# SCH_ESP-32_2024-10-27.net
KiCad netlist of a schematic drawn in EasyEDA
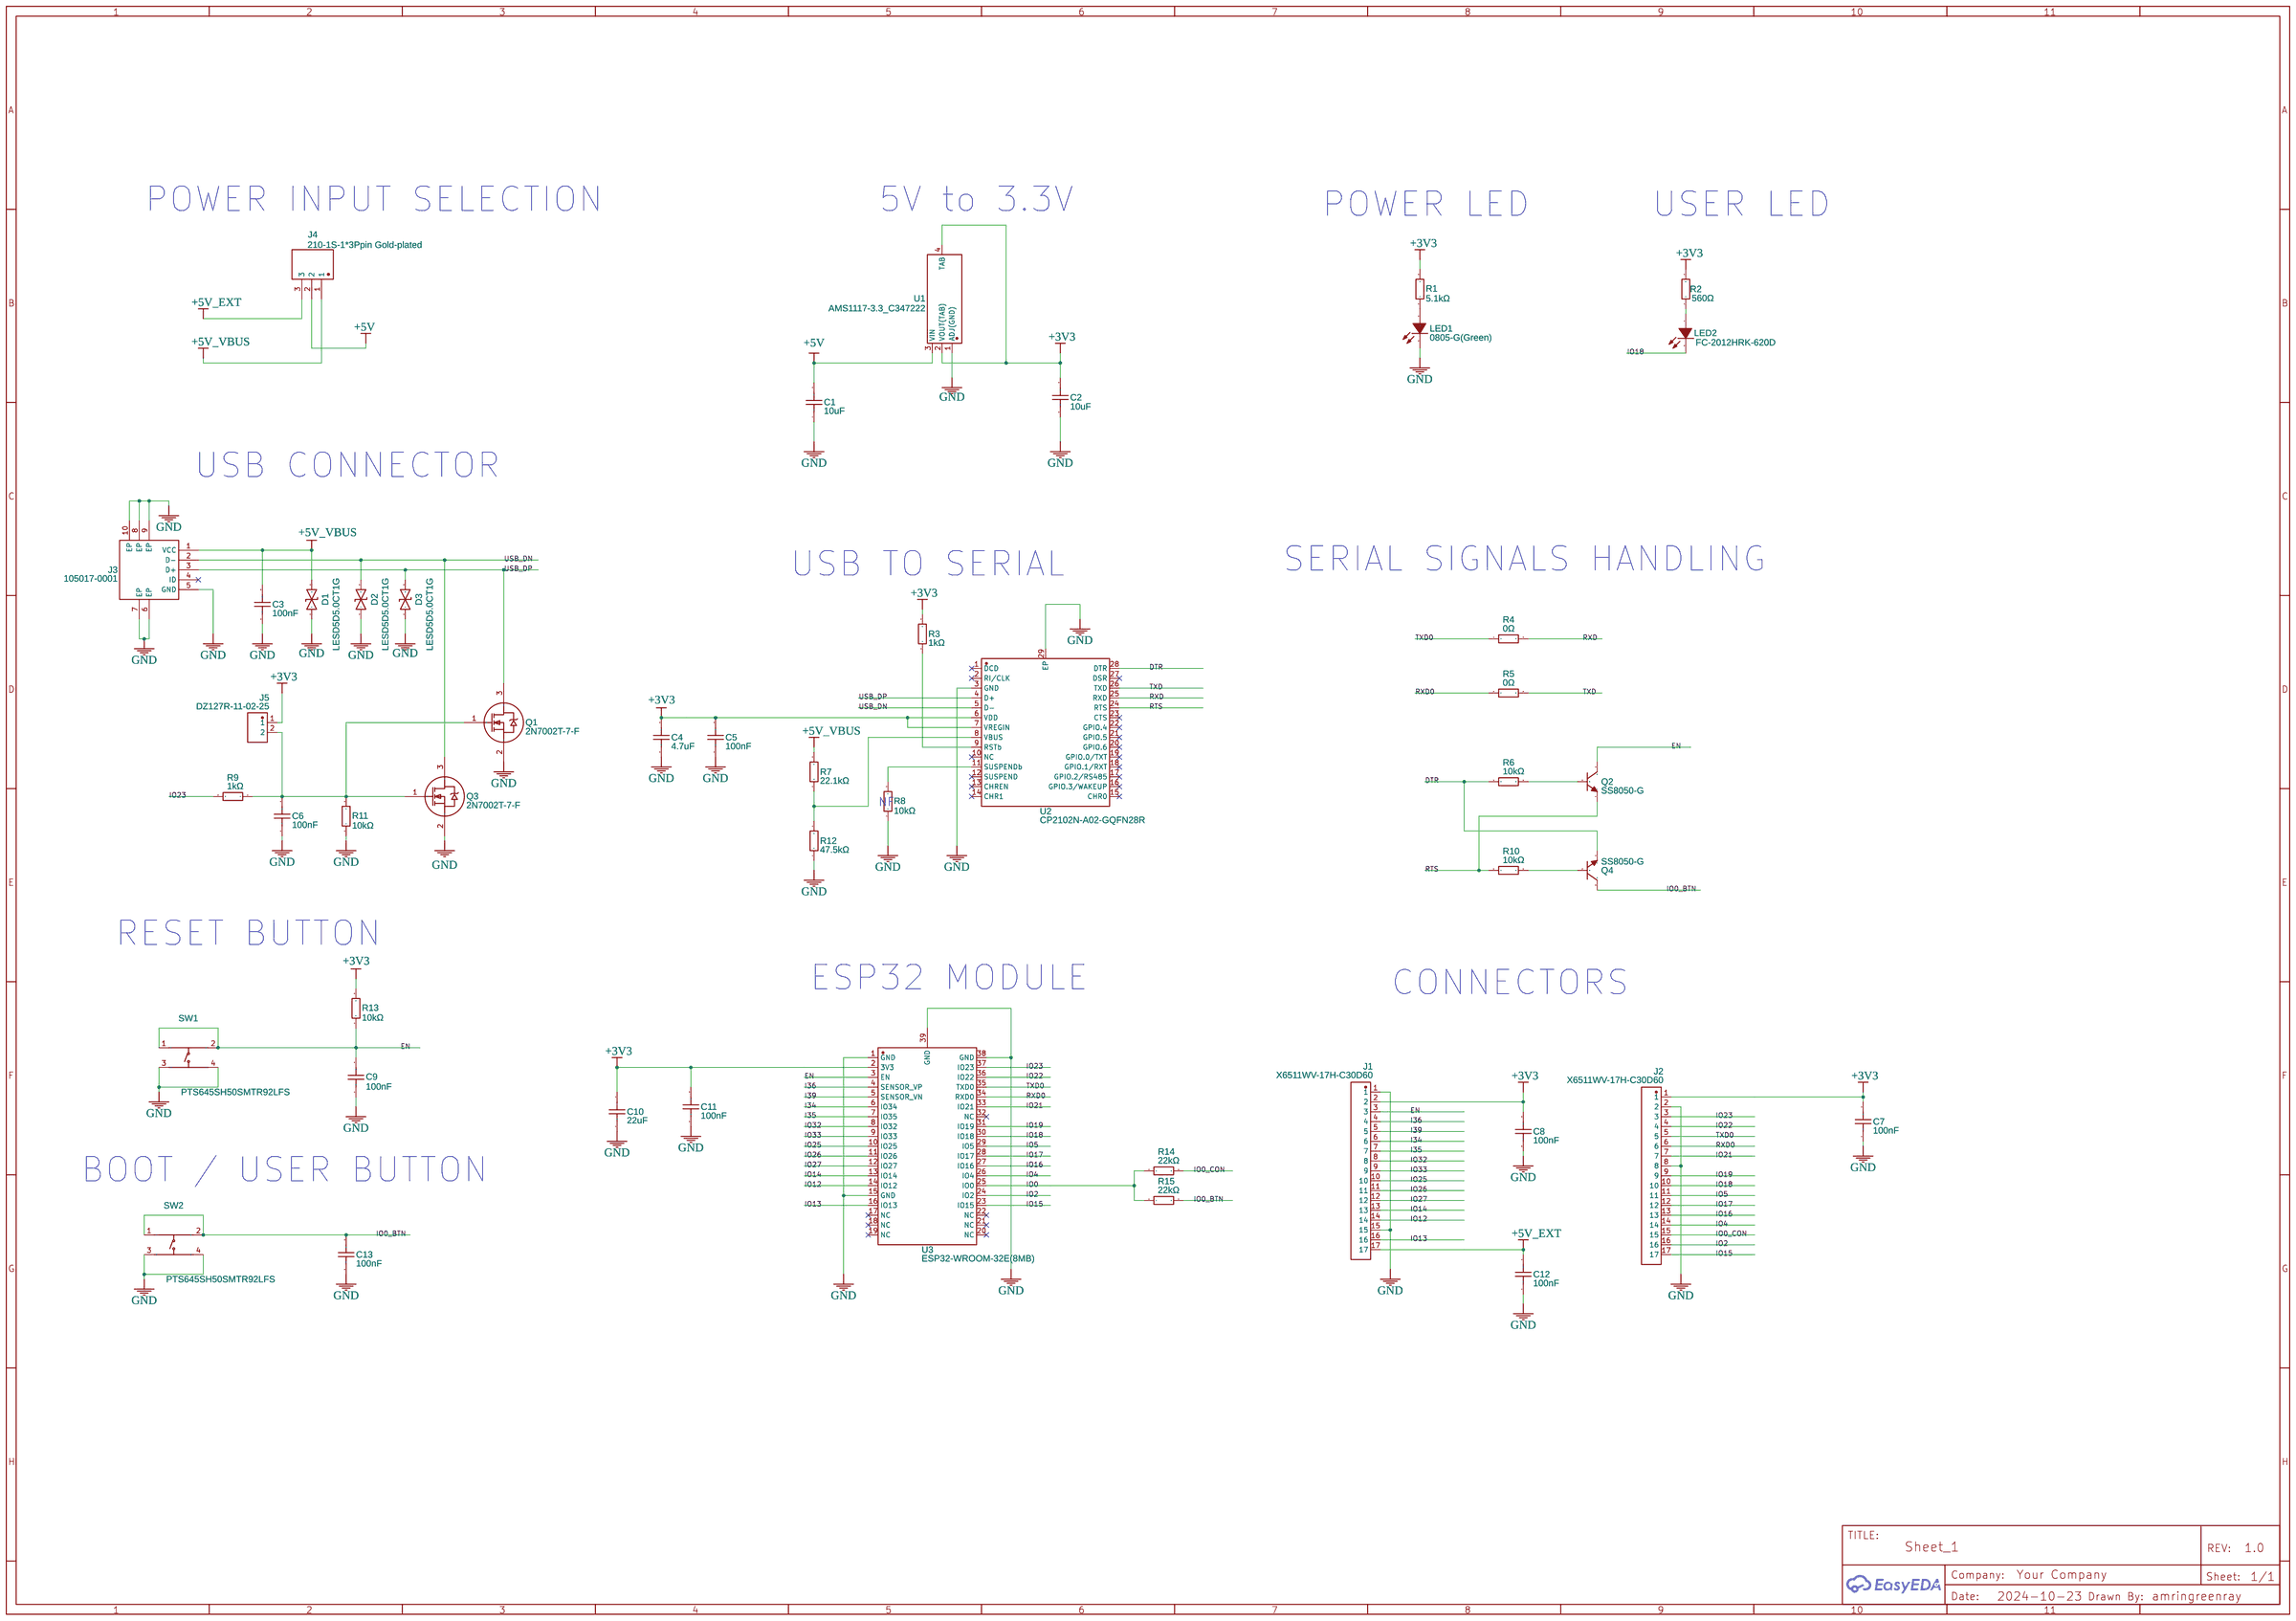
[diagram p0: schematic sheet]

(export (version "E")
  (design (tool "Eeschema 10.0.6"))
  (components
    (comp (ref "C1")
      (value "10uF")
      (fields
        (field (name "Manufacturer Part") "CL05A106MP5NUNC")
        (field (name "Manufacturer") "SAMSUNG(三星)")
      )
      (libsource (lib "") (part "CL05A106MP5NUNC_C315248"))
    )
    (comp (ref "C2")
      (value "10uF")
      (fields
        (field (name "Manufacturer Part") "CL05A106MP5NUNC")
        (field (name "Manufacturer") "SAMSUNG(三星)")
      )
      (libsource (lib "") (part "CL05A106MP5NUNC_C315248"))
    )
    (comp (ref "C3")
      (value "100nF")
      (fields
        (field (name "Manufacturer Part") "CL05B104KO5NNNC")
        (field (name "Manufacturer") "SAMSUNG(三星)")
      )
      (libsource (lib "") (part "CL05B104KO5NNNC"))
    )
    (comp (ref "C4")
      (value "4.7uF")
      (fields
        (field (name "Manufacturer Part") "CL05A475KP5NRNC")
        (field (name "Manufacturer") "SAMSUNG(三星)")
      )
      (libsource (lib "") (part "CL05A475KP5NRNC"))
    )
    (comp (ref "C5")
      (value "100nF")
      (fields
        (field (name "Manufacturer Part") "CL05B104KO5NNNC")
        (field (name "Manufacturer") "SAMSUNG(三星)")
      )
      (libsource (lib "") (part "CL05B104KO5NNNC"))
    )
    (comp (ref "C6")
      (value "100nF")
      (fields
        (field (name "Manufacturer Part") "CL05B104KO5NNNC")
        (field (name "Manufacturer") "SAMSUNG(三星)")
      )
      (libsource (lib "") (part "CL05B104KO5NNNC_1"))
    )
    (comp (ref "C7")
      (value "100nF")
      (fields
        (field (name "Manufacturer Part") "CL05B104KO5NNNC")
        (field (name "Manufacturer") "SAMSUNG(三星)")
      )
      (libsource (lib "") (part "CL05B104KO5NNNC"))
    )
    (comp (ref "C8")
      (value "100nF")
      (fields
        (field (name "Manufacturer Part") "CL05B104KO5NNNC")
        (field (name "Manufacturer") "SAMSUNG(三星)")
      )
      (libsource (lib "") (part "CL05B104KO5NNNC"))
    )
    (comp (ref "C9")
      (value "100nF")
      (fields
        (field (name "Manufacturer Part") "CL05B104KO5NNNC")
        (field (name "Manufacturer") "SAMSUNG(三星)")
      )
      (libsource (lib "") (part "CL05B104KO5NNNC"))
    )
    (comp (ref "C10")
      (value "22uF")
      (fields
        (field (name "Manufacturer Part") "CL21A226MAYNNNE")
        (field (name "Manufacturer") "SAMSUNG(三星)")
      )
      (libsource (lib "") (part "CL21A226MAYNNNE"))
    )
    (comp (ref "C11")
      (value "100nF")
      (fields
        (field (name "Manufacturer Part") "CL05B104KO5NNNC")
        (field (name "Manufacturer") "SAMSUNG(三星)")
      )
      (libsource (lib "") (part "CL05B104KO5NNNC"))
    )
    (comp (ref "C12")
      (value "100nF")
      (fields
        (field (name "Manufacturer Part") "CL05B104KO5NNNC")
        (field (name "Manufacturer") "SAMSUNG(三星)")
      )
      (libsource (lib "") (part "CL05B104KO5NNNC"))
    )
    (comp (ref "C13")
      (value "100nF")
      (fields
        (field (name "Manufacturer Part") "CL05B104KO5NNNC")
        (field (name "Manufacturer") "SAMSUNG(三星)")
      )
      (libsource (lib "") (part "CL05B104KO5NNNC"))
    )
    (comp (ref "D1")
      (value "LESD5D5.0CT1G")
      (fields (field (name "Manufacturer") "LRC(乐山无线电)"))
      (libsource (lib "") (part "LESD5D5.0CT1G"))
    )
    (comp (ref "D2")
      (value "LESD5D5.0CT1G")
      (fields (field (name "Manufacturer") "LRC(乐山无线电)"))
      (libsource (lib "") (part "LESD5D5.0CT1G"))
    )
    (comp (ref "D3")
      (value "LESD5D5.0CT1G")
      (fields (field (name "Manufacturer") "LRC(乐山无线电)"))
      (libsource (lib "") (part "LESD5D5.0CT1G"))
    )
    (comp (ref "J1")
      (value "X6511WV-17H-C30D60")
      (fields
        (field (name "Manufacturer Part") "X6511WV-17H-C60D30")
        (field (name "Manufacturer") "XKB Connection(中国星坤)")
      )
      (libsource (lib "") (part "X6511WV-17H-C30D60"))
    )
    (comp (ref "J2")
      (value "X6511WV-17H-C30D60")
      (fields
        (field (name "Manufacturer Part") "X6511WV-17H-C60D30")
        (field (name "Manufacturer") "XKB Connection(中国星坤)")
      )
      (libsource (lib "") (part "X6511WV-17H-C30D60"))
    )
    (comp (ref "J3")
      (value "105017-0001")
      (fields (field (name "Manufacturer Part") "1050170001") (field (name "Manufacturer") "MOLEX"))
      (libsource (lib "") (part "105017-0001"))
    )
    (comp (ref "J4")
      (value "210-1S-1*3Ppin Gold-plated")
      (fields (field (name "Manufacturer Part") "B-2101S03P-A110") (field (name "Manufacturer") "Ckmtw(灿科盟)"))
      (libsource (lib "") (part "210-1S-1*3Ppin Gold-plated"))
    )
    (comp (ref "J5")
      (value "DZ127R-11-02-25")
      (fields (field (name "Manufacturer") "DEALON(德艺隆)"))
      (libsource (lib "") (part "DZ127R-11-02-25"))
    )
    (comp (ref "LED1")
      (value "0805-G(Green)")
      (fields (field (name "Manufacturer Part") "LEDGREEN0805"))
      (libsource (lib "") (part "LEDGREEN0805"))
    )
    (comp (ref "LED2")
      (value "FC-2012HRK-620D")
      (fields (field (name "Manufacturer Part") "NCD0805R1") (field (name "Manufacturer") "国星光电"))
      (libsource (lib "") (part "FC-2012HRK-620D"))
    )
    (comp (ref "Q1")
      (value "2N7002T-7-F")
      (fields (field (name "Manufacturer") "DIODES(美台)"))
      (libsource (lib "") (part "2N7002T-7-F"))
    )
    (comp (ref "Q2")
      (value "SS8050-G")
      (fields (field (name "Manufacturer") "CJ(江苏长电/长晶)"))
      (libsource (lib "") (part "SS8050-G"))
    )
    (comp (ref "Q3")
      (value "2N7002T-7-F")
      (fields (field (name "Manufacturer") "DIODES(美台)"))
      (libsource (lib "") (part "2N7002T-7-F"))
    )
    (comp (ref "Q4")
      (value "SS8050-G")
      (fields (field (name "Manufacturer") "CJ(江苏长电/长晶)"))
      (libsource (lib "") (part "SS8050-G_1"))
    )
    (comp (ref "R1")
      (value "5.1kΩ")
      (fields
        (field (name "Manufacturer Part") "0402WGF5101TCE")
        (field (name "Manufacturer") "UNI-ROYAL(厚声)")
      )
      (libsource (lib "") (part "0402WGF5101TCE"))
    )
    (comp (ref "R2")
      (value "560Ω")
      (fields
        (field (name "Manufacturer Part") "0402WGF5600TCE")
        (field (name "Manufacturer") "UNI-ROYAL(厚声)")
      )
      (libsource (lib "") (part "0402WGF5600TCE"))
    )
    (comp (ref "R3")
      (value "1kΩ")
      (fields
        (field (name "Manufacturer Part") "0402WGF1001TCE")
        (field (name "Manufacturer") "UNI-ROYAL(厚声)")
      )
      (libsource (lib "") (part "0402WGF1001TCE"))
    )
    (comp (ref "R4")
      (value "0Ω")
      (fields
        (field (name "Manufacturer Part") "0402WGF0000TCE")
        (field (name "Manufacturer") "UNI-ROYAL(厚声)")
      )
      (libsource (lib "") (part "0402WGF0000TCE"))
    )
    (comp (ref "R5")
      (value "0Ω")
      (fields
        (field (name "Manufacturer Part") "0402WGF0000TCE")
        (field (name "Manufacturer") "UNI-ROYAL(厚声)")
      )
      (libsource (lib "") (part "0402WGF0000TCE"))
    )
    (comp (ref "R6")
      (value "10kΩ")
      (fields
        (field (name "Manufacturer Part") "0402WGF1002TCE")
        (field (name "Manufacturer") "UNI-ROYAL(厚声)")
      )
      (libsource (lib "") (part "0402WGF1002TCE"))
    )
    (comp (ref "R7")
      (value "22.1kΩ")
      (fields
        (field (name "Manufacturer Part") "0402WGF2212TCE")
        (field (name "Manufacturer") "UNI-ROYAL(厚声)")
      )
      (libsource (lib "") (part "0402WGF2212TCE"))
    )
    (comp (ref "R8")
      (value "10kΩ")
      (fields
        (field (name "Manufacturer Part") "0402WGF1002TCE")
        (field (name "Manufacturer") "UNI-ROYAL(厚声)")
      )
      (libsource (lib "") (part "0402WGF1002TCE_1"))
    )
    (comp (ref "R9")
      (value "1kΩ")
      (fields
        (field (name "Manufacturer Part") "0402WGF1001TCE")
        (field (name "Manufacturer") "UNI-ROYAL(厚声)")
      )
      (libsource (lib "") (part "0402WGF1001TCE_1"))
    )
    (comp (ref "R10")
      (value "10kΩ")
      (fields
        (field (name "Manufacturer Part") "0402WGF1002TCE")
        (field (name "Manufacturer") "UNI-ROYAL(厚声)")
      )
      (libsource (lib "") (part "0402WGF1002TCE"))
    )
    (comp (ref "R11")
      (value "10kΩ")
      (fields
        (field (name "Manufacturer Part") "0402WGF1002TCE")
        (field (name "Manufacturer") "UNI-ROYAL(厚声)")
      )
      (libsource (lib "") (part "0402WGF1002TCE_1"))
    )
    (comp (ref "R12")
      (value "47.5kΩ")
      (fields
        (field (name "Manufacturer Part") "0402WGF4752TCE")
        (field (name "Manufacturer") "UNI-ROYAL(厚声)")
      )
      (libsource (lib "") (part "0402WGF4752TCE"))
    )
    (comp (ref "R13")
      (value "10kΩ")
      (fields
        (field (name "Manufacturer Part") "0402WGF1002TCE")
        (field (name "Manufacturer") "UNI-ROYAL(厚声)")
      )
      (libsource (lib "") (part "0402WGF1002TCE_1"))
    )
    (comp (ref "R14")
      (value "22kΩ")
      (fields
        (field (name "Manufacturer Part") "0402WGF2202TCE")
        (field (name "Manufacturer") "UNI-ROYAL(厚声)")
      )
      (libsource (lib "") (part "0402WGF2202TCE"))
    )
    (comp (ref "R15")
      (value "22kΩ")
      (fields
        (field (name "Manufacturer Part") "0402WGF2202TCE")
        (field (name "Manufacturer") "UNI-ROYAL(厚声)")
      )
      (libsource (lib "") (part "0402WGF2202TCE"))
    )
    (comp (ref "SW1")
      (value "PTS645SH50SMTR92LFS")
      (fields (field (name "Manufacturer") "C&K"))
      (libsource (lib "") (part "PTS645SH50SMTR92LFS"))
    )
    (comp (ref "SW2")
      (value "PTS645SH50SMTR92LFS")
      (fields (field (name "Manufacturer") "C&K"))
      (libsource (lib "") (part "PTS645SH50SMTR92LFS"))
    )
    (comp (ref "U1")
      (value "AMS1117-3.3_C347222")
      (fields (field (name "Manufacturer Part") "AMS1117-3.3") (field (name "Manufacturer") "UMW(友台半导体)"))
      (libsource (lib "") (part "AMS1117-3.3_C347222"))
    )
    (comp (ref "U2")
      (value "CP2102N-A02-GQFN28R")
      (fields (field (name "Manufacturer") "SKYWORKS/SILICON LABS(芯科)"))
      (libsource (lib "") (part "CP2102N-A02-GQFN28R"))
    )
    (comp (ref "U3")
      (value "ESP32-WROOM-32E(8MB)")
      (fields
        (field (name "Manufacturer Part") "ESP32-WROOM-32E-N8")
        (field (name "Manufacturer") "ESPRESSIF(乐鑫)")
      )
      (libsource (lib "") (part "ESP32-WROOM-32E(8MB)"))
    )
  )
  (nets
    (net (code "1") (name "+3V3") (class "Default")
      (node (ref "C10") (pin "2") (pinfunction "2_2") (pintype "unspecified"))
      (node (ref "C11") (pin "2") (pinfunction "2_2") (pintype "unspecified"))
      (node (ref "C2") (pin "2") (pinfunction "2_2") (pintype "unspecified"))
      (node (ref "C4") (pin "1") (pinfunction "1_1") (pintype "unspecified"))
      (node (ref "C5") (pin "2") (pinfunction "2_2") (pintype "unspecified"))
      (node (ref "C7") (pin "2") (pinfunction "2_2") (pintype "unspecified"))
      (node (ref "C8") (pin "2") (pinfunction "2_2") (pintype "unspecified"))
      (node (ref "J1") (pin "2") (pinfunction "2_2") (pintype "unspecified"))
      (node (ref "J2") (pin "1") (pinfunction "1_1") (pintype "unspecified"))
      (node (ref "J5") (pin "1") (pinfunction "1_1") (pintype "unspecified"))
      (node (ref "R1") (pin "2") (pinfunction "2_2") (pintype "input"))
      (node (ref "R13") (pin "2") (pinfunction "2_2") (pintype "input"))
      (node (ref "R2") (pin "2") (pinfunction "2_2") (pintype "input"))
      (node (ref "R3") (pin "2") (pinfunction "2_2") (pintype "input"))
      (node (ref "U1") (pin "2") (pinfunction "VOUT(TAB)_2") (pintype "unspecified"))
      (node (ref "U1") (pin "4") (pinfunction "TAB_4") (pintype "unspecified"))
      (node (ref "U2") (pin "6") (pinfunction "VDD_6") (pintype "unspecified"))
      (node (ref "U2") (pin "7") (pinfunction "VREGIN_7") (pintype "unspecified"))
      (node (ref "U3") (pin "2") (pinfunction "3V3_2") (pintype "unspecified"))
    )
    (net (code "2") (name "+5V") (class "Default")
      (node (ref "C1") (pin "2") (pinfunction "2_2") (pintype "unspecified"))
      (node (ref "J4") (pin "2") (pinfunction "2_2") (pintype "unspecified"))
      (node (ref "U1") (pin "3") (pinfunction "VIN_3") (pintype "unspecified"))
    )
    (net (code "3") (name "+5V_EXT") (class "Default")
      (node (ref "C12") (pin "2") (pinfunction "2_2") (pintype "unspecified"))
      (node (ref "J1") (pin "17") (pinfunction "17_17") (pintype "unspecified"))
      (node (ref "J4") (pin "3") (pinfunction "3_3") (pintype "unspecified"))
    )
    (net (code "4") (name "+5V_VBUS") (class "Default")
      (node (ref "C3") (pin "2") (pinfunction "2_2") (pintype "unspecified"))
      (node (ref "D1") (pin "2") (pinfunction "2_2") (pintype "unspecified"))
      (node (ref "J3") (pin "1") (pinfunction "VCC_1") (pintype "unspecified"))
      (node (ref "J4") (pin "1") (pinfunction "1_1") (pintype "unspecified"))
      (node (ref "R7") (pin "2") (pinfunction "2_2") (pintype "input"))
    )
    (net (code "5") (name "/DTR") (class "Default")
      (node (ref "Q4") (pin "2") (pinfunction "E_2") (pintype "input"))
      (node (ref "R6") (pin "1") (pinfunction "1_1") (pintype "input"))
      (node (ref "U2") (pin "28") (pinfunction "DTR_28") (pintype "unspecified"))
    )
    (net (code "6") (name "/EN") (class "Default")
      (node (ref "C9") (pin "2") (pinfunction "2_2") (pintype "unspecified"))
      (node (ref "J1") (pin "3") (pinfunction "3_3") (pintype "unspecified"))
      (node (ref "Q2") (pin "3") (pinfunction "C_3") (pintype "input"))
      (node (ref "R13") (pin "1") (pinfunction "1_1") (pintype "input"))
      (node (ref "SW1") (pin "1") (pinfunction "1_1") (pintype "unspecified"))
      (node (ref "SW1") (pin "2") (pinfunction "2_2") (pintype "unspecified"))
      (node (ref "U3") (pin "3") (pinfunction "EN_3") (pintype "unspecified"))
    )
    (net (code "7") (name "/I34") (class "Default")
      (node (ref "J1") (pin "6") (pinfunction "6_6") (pintype "unspecified"))
      (node (ref "U3") (pin "6") (pinfunction "IO34_6") (pintype "unspecified"))
    )
    (net (code "8") (name "/I35") (class "Default")
      (node (ref "J1") (pin "7") (pinfunction "7_7") (pintype "unspecified"))
      (node (ref "U3") (pin "7") (pinfunction "IO35_7") (pintype "unspecified"))
    )
    (net (code "9") (name "/I36") (class "Default")
      (node (ref "J1") (pin "4") (pinfunction "4_4") (pintype "unspecified"))
      (node (ref "U3") (pin "4") (pinfunction "SENSOR_VP_4") (pintype "unspecified"))
    )
    (net (code "10") (name "/I39") (class "Default")
      (node (ref "J1") (pin "5") (pinfunction "5_5") (pintype "unspecified"))
      (node (ref "U3") (pin "5") (pinfunction "SENSOR_VN_5") (pintype "unspecified"))
    )
    (net (code "11") (name "/IO0") (class "Default")
      (node (ref "R14") (pin "1") (pinfunction "1_1") (pintype "input"))
      (node (ref "R15") (pin "1") (pinfunction "1_1") (pintype "input"))
      (node (ref "U3") (pin "25") (pinfunction "IO0_25") (pintype "unspecified"))
    )
    (net (code "12") (name "/IO0_BTN") (class "Default")
      (node (ref "C13") (pin "2") (pinfunction "2_2") (pintype "unspecified"))
      (node (ref "Q4") (pin "3") (pinfunction "C_3") (pintype "input"))
      (node (ref "R15") (pin "2") (pinfunction "2_2") (pintype "input"))
      (node (ref "SW2") (pin "1") (pinfunction "1_1") (pintype "unspecified"))
      (node (ref "SW2") (pin "2") (pinfunction "2_2") (pintype "unspecified"))
    )
    (net (code "13") (name "/IO0_CON") (class "Default")
      (node (ref "J2") (pin "15") (pinfunction "15_15") (pintype "unspecified"))
      (node (ref "R14") (pin "2") (pinfunction "2_2") (pintype "input"))
    )
    (net (code "14") (name "/IO2") (class "Default")
      (node (ref "J2") (pin "16") (pinfunction "16_16") (pintype "unspecified"))
      (node (ref "U3") (pin "24") (pinfunction "IO2_24") (pintype "unspecified"))
    )
    (net (code "15") (name "/IO4") (class "Default")
      (node (ref "J2") (pin "14") (pinfunction "14_14") (pintype "unspecified"))
      (node (ref "U3") (pin "26") (pinfunction "IO4_26") (pintype "unspecified"))
    )
    (net (code "16") (name "/IO5") (class "Default")
      (node (ref "J2") (pin "11") (pinfunction "11_11") (pintype "unspecified"))
      (node (ref "U3") (pin "29") (pinfunction "IO5_29") (pintype "unspecified"))
    )
    (net (code "17") (name "/IO12") (class "Default")
      (node (ref "J1") (pin "14") (pinfunction "14_14") (pintype "unspecified"))
      (node (ref "U3") (pin "14") (pinfunction "IO12_14") (pintype "unspecified"))
    )
    (net (code "18") (name "/IO13") (class "Default")
      (node (ref "J1") (pin "16") (pinfunction "16_16") (pintype "unspecified"))
      (node (ref "U3") (pin "16") (pinfunction "IO13_16") (pintype "unspecified"))
    )
    (net (code "19") (name "/IO14") (class "Default")
      (node (ref "J1") (pin "13") (pinfunction "13_13") (pintype "unspecified"))
      (node (ref "U3") (pin "13") (pinfunction "IO14_13") (pintype "unspecified"))
    )
    (net (code "20") (name "/IO15") (class "Default")
      (node (ref "J2") (pin "17") (pinfunction "17_17") (pintype "unspecified"))
      (node (ref "U3") (pin "23") (pinfunction "IO15_23") (pintype "unspecified"))
    )
    (net (code "21") (name "/IO16") (class "Default")
      (node (ref "J2") (pin "13") (pinfunction "13_13") (pintype "unspecified"))
      (node (ref "U3") (pin "27") (pinfunction "IO16_27") (pintype "unspecified"))
    )
    (net (code "22") (name "/IO17") (class "Default")
      (node (ref "J2") (pin "12") (pinfunction "12_12") (pintype "unspecified"))
      (node (ref "U3") (pin "28") (pinfunction "IO17_28") (pintype "unspecified"))
    )
    (net (code "23") (name "/IO18") (class "Default")
      (node (ref "J2") (pin "10") (pinfunction "10_10") (pintype "unspecified"))
      (node (ref "LED2") (pin "2") (pinfunction "-_2") (pintype "unspecified"))
      (node (ref "U3") (pin "30") (pinfunction "IO18_30") (pintype "unspecified"))
    )
    (net (code "24") (name "/IO19") (class "Default")
      (node (ref "J2") (pin "9") (pinfunction "9_9") (pintype "unspecified"))
      (node (ref "U3") (pin "31") (pinfunction "IO19_31") (pintype "unspecified"))
    )
    (net (code "25") (name "/IO21") (class "Default")
      (node (ref "J2") (pin "7") (pinfunction "7_7") (pintype "unspecified"))
      (node (ref "U3") (pin "33") (pinfunction "IO21_33") (pintype "unspecified"))
    )
    (net (code "26") (name "/IO22") (class "Default")
      (node (ref "J2") (pin "4") (pinfunction "4_4") (pintype "unspecified"))
      (node (ref "U3") (pin "36") (pinfunction "IO22_36") (pintype "unspecified"))
    )
    (net (code "27") (name "/IO23") (class "Default")
      (node (ref "J2") (pin "3") (pinfunction "3_3") (pintype "unspecified"))
      (node (ref "R9") (pin "2") (pinfunction "2_2") (pintype "input"))
      (node (ref "U3") (pin "37") (pinfunction "IO23_37") (pintype "unspecified"))
    )
    (net (code "28") (name "/IO25") (class "Default")
      (node (ref "J1") (pin "10") (pinfunction "10_10") (pintype "unspecified"))
      (node (ref "U3") (pin "10") (pinfunction "IO25_10") (pintype "unspecified"))
    )
    (net (code "29") (name "/IO26") (class "Default")
      (node (ref "J1") (pin "11") (pinfunction "11_11") (pintype "unspecified"))
      (node (ref "U3") (pin "11") (pinfunction "IO26_11") (pintype "unspecified"))
    )
    (net (code "30") (name "/IO27") (class "Default")
      (node (ref "J1") (pin "12") (pinfunction "12_12") (pintype "unspecified"))
      (node (ref "U3") (pin "12") (pinfunction "IO27_12") (pintype "unspecified"))
    )
    (net (code "31") (name "/IO32") (class "Default")
      (node (ref "J1") (pin "8") (pinfunction "8_8") (pintype "unspecified"))
      (node (ref "U3") (pin "8") (pinfunction "IO32_8") (pintype "unspecified"))
    )
    (net (code "32") (name "/IO33") (class "Default")
      (node (ref "J1") (pin "9") (pinfunction "9_9") (pintype "unspecified"))
      (node (ref "U3") (pin "9") (pinfunction "IO33_9") (pintype "unspecified"))
    )
    (net (code "33") (name "/RTS") (class "Default")
      (node (ref "Q2") (pin "2") (pinfunction "E_2") (pintype "input"))
      (node (ref "R10") (pin "1") (pinfunction "1_1") (pintype "input"))
      (node (ref "U2") (pin "24") (pinfunction "RTS_24") (pintype "unspecified"))
    )
    (net (code "34") (name "/RXD") (class "Default")
      (node (ref "R4") (pin "2") (pinfunction "2_2") (pintype "input"))
      (node (ref "U2") (pin "25") (pinfunction "RXD_25") (pintype "unspecified"))
    )
    (net (code "35") (name "/RXD0") (class "Default")
      (node (ref "J2") (pin "6") (pinfunction "6_6") (pintype "unspecified"))
      (node (ref "R5") (pin "1") (pinfunction "1_1") (pintype "input"))
      (node (ref "U3") (pin "34") (pinfunction "RXD0_34") (pintype "unspecified"))
    )
    (net (code "36") (name "/TXD") (class "Default")
      (node (ref "R5") (pin "2") (pinfunction "2_2") (pintype "input"))
      (node (ref "U2") (pin "26") (pinfunction "TXD_26") (pintype "unspecified"))
    )
    (net (code "37") (name "/TXD0") (class "Default")
      (node (ref "J2") (pin "5") (pinfunction "5_5") (pintype "unspecified"))
      (node (ref "R4") (pin "1") (pinfunction "1_1") (pintype "input"))
      (node (ref "U3") (pin "35") (pinfunction "TXD0_35") (pintype "unspecified"))
    )
    (net (code "38") (name "/USB_DN") (class "Default")
      (node (ref "D2") (pin "2") (pinfunction "2_2") (pintype "unspecified"))
      (node (ref "J3") (pin "2") (pinfunction "D-_2") (pintype "unspecified"))
      (node (ref "Q3") (pin "3") (pinfunction "D_3") (pintype "unspecified"))
      (node (ref "U2") (pin "5") (pinfunction "D-_5") (pintype "unspecified"))
    )
    (net (code "39") (name "/USB_DP") (class "Default")
      (node (ref "D3") (pin "2") (pinfunction "2_2") (pintype "unspecified"))
      (node (ref "J3") (pin "3") (pinfunction "D+_3") (pintype "unspecified"))
      (node (ref "Q1") (pin "3") (pinfunction "D_3") (pintype "unspecified"))
      (node (ref "U2") (pin "4") (pinfunction "D+_4") (pintype "unspecified"))
    )
    (net (code "40") (name "GND") (class "Default")
      (node (ref "C1") (pin "1") (pinfunction "1_1") (pintype "unspecified"))
      (node (ref "C10") (pin "1") (pinfunction "1_1") (pintype "unspecified"))
      (node (ref "C11") (pin "1") (pinfunction "1_1") (pintype "unspecified"))
      (node (ref "C12") (pin "1") (pinfunction "1_1") (pintype "unspecified"))
      (node (ref "C13") (pin "1") (pinfunction "1_1") (pintype "unspecified"))
      (node (ref "C2") (pin "1") (pinfunction "1_1") (pintype "unspecified"))
      (node (ref "C3") (pin "1") (pinfunction "1_1") (pintype "unspecified"))
      (node (ref "C4") (pin "2") (pinfunction "2_2") (pintype "unspecified"))
      (node (ref "C5") (pin "1") (pinfunction "1_1") (pintype "unspecified"))
      (node (ref "C6") (pin "2") (pinfunction "2_2") (pintype "unspecified"))
      (node (ref "C7") (pin "1") (pinfunction "1_1") (pintype "unspecified"))
      (node (ref "C8") (pin "1") (pinfunction "1_1") (pintype "unspecified"))
      (node (ref "C9") (pin "1") (pinfunction "1_1") (pintype "unspecified"))
      (node (ref "D1") (pin "1") (pinfunction "1_1") (pintype "unspecified"))
      (node (ref "D2") (pin "1") (pinfunction "1_1") (pintype "unspecified"))
      (node (ref "D3") (pin "1") (pinfunction "1_1") (pintype "unspecified"))
      (node (ref "J1") (pin "1") (pinfunction "1_1") (pintype "unspecified"))
      (node (ref "J1") (pin "15") (pinfunction "15_15") (pintype "unspecified"))
      (node (ref "J2") (pin "2") (pinfunction "2_2") (pintype "unspecified"))
      (node (ref "J2") (pin "8") (pinfunction "8_8") (pintype "unspecified"))
      (node (ref "J3") (pin "10") (pinfunction "EP_10") (pintype "unspecified"))
      (node (ref "J3") (pin "5") (pinfunction "GND_5") (pintype "unspecified"))
      (node (ref "J3") (pin "6") (pinfunction "EP_6") (pintype "unspecified"))
      (node (ref "J3") (pin "7") (pinfunction "EP_7") (pintype "unspecified"))
      (node (ref "J3") (pin "8") (pinfunction "EP_8") (pintype "unspecified"))
      (node (ref "J3") (pin "9") (pinfunction "EP_9") (pintype "unspecified"))
      (node (ref "LED1") (pin "2") (pinfunction "K_2") (pintype "unspecified"))
      (node (ref "Q1") (pin "2") (pinfunction "S_2") (pintype "unspecified"))
      (node (ref "Q3") (pin "2") (pinfunction "S_2") (pintype "unspecified"))
      (node (ref "R11") (pin "1") (pinfunction "1_1") (pintype "input"))
      (node (ref "R12") (pin "1") (pinfunction "1_1") (pintype "input"))
      (node (ref "R8") (pin "1") (pinfunction "1_1") (pintype "input"))
      (node (ref "SW1") (pin "3") (pinfunction "3_3") (pintype "unspecified"))
      (node (ref "SW1") (pin "4") (pinfunction "4_4") (pintype "unspecified"))
      (node (ref "SW2") (pin "3") (pinfunction "3_3") (pintype "unspecified"))
      (node (ref "SW2") (pin "4") (pinfunction "4_4") (pintype "unspecified"))
      (node (ref "U1") (pin "1") (pinfunction "ADJ(GND)_1") (pintype "unspecified"))
      (node (ref "U2") (pin "29") (pinfunction "EP_29") (pintype "unspecified"))
      (node (ref "U2") (pin "3") (pinfunction "GND_3") (pintype "unspecified"))
      (node (ref "U3") (pin "1") (pinfunction "GND_1") (pintype "unspecified"))
      (node (ref "U3") (pin "15") (pinfunction "GND_15") (pintype "unspecified"))
      (node (ref "U3") (pin "38") (pinfunction "GND_38") (pintype "unspecified"))
      (node (ref "U3") (pin "39") (pinfunction "GND_39") (pintype "unspecified"))
    )
    (net (code "41") (name "Net-(LED1-A)") (class "Default")
      (node (ref "LED1") (pin "1") (pinfunction "A_1") (pintype "unspecified"))
      (node (ref "R1") (pin "1") (pinfunction "1_1") (pintype "input"))
    )
    (net (code "42") (name "Net-(LED2-+)") (class "Default")
      (node (ref "LED2") (pin "1") (pinfunction "+_1") (pintype "unspecified"))
      (node (ref "R2") (pin "1") (pinfunction "1_1") (pintype "input"))
    )
    (net (code "43") (name "Net-(Q1-G)") (class "Default")
      (node (ref "C6") (pin "1") (pinfunction "1_1") (pintype "unspecified"))
      (node (ref "J5") (pin "2") (pinfunction "2_2") (pintype "unspecified"))
      (node (ref "Q1") (pin "1") (pinfunction "G_1") (pintype "unspecified"))
      (node (ref "Q3") (pin "1") (pinfunction "G_1") (pintype "unspecified"))
      (node (ref "R11") (pin "2") (pinfunction "2_2") (pintype "input"))
      (node (ref "R9") (pin "1") (pinfunction "1_1") (pintype "input"))
    )
    (net (code "44") (name "Net-(Q2-B)") (class "Default")
      (node (ref "Q2") (pin "1") (pinfunction "B_1") (pintype "input"))
      (node (ref "R6") (pin "2") (pinfunction "2_2") (pintype "input"))
    )
    (net (code "45") (name "Net-(Q4-B)") (class "Default")
      (node (ref "Q4") (pin "1") (pinfunction "B_1") (pintype "input"))
      (node (ref "R10") (pin "2") (pinfunction "2_2") (pintype "input"))
    )
    (net (code "46") (name "Net-(U2-RSTb)") (class "Default")
      (node (ref "R3") (pin "1") (pinfunction "1_1") (pintype "input"))
      (node (ref "U2") (pin "9") (pinfunction "RSTb_9") (pintype "unspecified"))
    )
    (net (code "47") (name "Net-(U2-SUSPENDb)") (class "Default")
      (node (ref "R8") (pin "2") (pinfunction "2_2") (pintype "input"))
      (node (ref "U2") (pin "11") (pinfunction "SUSPENDb_11") (pintype "unspecified"))
    )
    (net (code "48") (name "Net-(U2-VBUS)") (class "Default")
      (node (ref "R12") (pin "2") (pinfunction "2_2") (pintype "input"))
      (node (ref "R7") (pin "1") (pinfunction "1_1") (pintype "input"))
      (node (ref "U2") (pin "8") (pinfunction "VBUS_8") (pintype "unspecified"))
    )
    (net (code "49") (name "unconnected-(J3-ID-Pad4)") (class "Default")
      (node (ref "J3") (pin "4") (pinfunction "ID_4") (pintype "unspecified+no_connect"))
    )
    (net (code "50") (name "unconnected-(U2-CHR0-Pad15)") (class "Default")
      (node (ref "U2") (pin "15") (pinfunction "CHR0_15") (pintype "unspecified+no_connect"))
    )
    (net (code "51") (name "unconnected-(U2-CHR1-Pad14)") (class "Default")
      (node (ref "U2") (pin "14") (pinfunction "CHR1_14") (pintype "unspecified+no_connect"))
    )
    (net (code "52") (name "unconnected-(U2-CHREN-Pad13)") (class "Default")
      (node (ref "U2") (pin "13") (pinfunction "CHREN_13") (pintype "unspecified+no_connect"))
    )
    (net (code "53") (name "unconnected-(U2-CTS-Pad23)") (class "Default")
      (node (ref "U2") (pin "23") (pinfunction "CTS_23") (pintype "unspecified+no_connect"))
    )
    (net (code "54") (name "unconnected-(U2-DCD-Pad1)") (class "Default")
      (node (ref "U2") (pin "1") (pinfunction "DCD_1") (pintype "unspecified+no_connect"))
    )
    (net (code "55") (name "unconnected-(U2-DSR-Pad27)") (class "Default")
      (node (ref "U2") (pin "27") (pinfunction "DSR_27") (pintype "unspecified+no_connect"))
    )
    (net (code "56") (name "unconnected-(U2-GPIO.0{slash}TXT-Pad19)") (class "Default")
      (node (ref "U2") (pin "19") (pinfunction "GPIO.0/TXT_19") (pintype "unspecified+no_connect"))
    )
    (net (code "57") (name "unconnected-(U2-GPIO.1{slash}RXT-Pad18)") (class "Default")
      (node (ref "U2") (pin "18") (pinfunction "GPIO.1/RXT_18") (pintype "unspecified+no_connect"))
    )
    (net (code "58") (name "unconnected-(U2-GPIO.2{slash}RS485-Pad17)") (class "Default")
      (node (ref "U2") (pin "17") (pinfunction "GPIO.2/RS485_17") (pintype "unspecified+no_connect"))
    )
    (net (code "59") (name "unconnected-(U2-GPIO.3{slash}WAKEUP-Pad16)") (class "Default")
      (node (ref "U2") (pin "16") (pinfunction "GPIO.3/WAKEUP_16") (pintype "unspecified+no_connect"))
    )
    (net (code "60") (name "unconnected-(U2-GPIO.4-Pad22)") (class "Default")
      (node (ref "U2") (pin "22") (pinfunction "GPIO.4_22") (pintype "unspecified+no_connect"))
    )
    (net (code "61") (name "unconnected-(U2-GPIO.5-Pad21)") (class "Default")
      (node (ref "U2") (pin "21") (pinfunction "GPIO.5_21") (pintype "unspecified+no_connect"))
    )
    (net (code "62") (name "unconnected-(U2-GPIO.6-Pad20)") (class "Default")
      (node (ref "U2") (pin "20") (pinfunction "GPIO.6_20") (pintype "unspecified+no_connect"))
    )
    (net (code "63") (name "unconnected-(U2-NC-Pad10)") (class "Default")
      (node (ref "U2") (pin "10") (pinfunction "NC_10") (pintype "unspecified+no_connect"))
    )
    (net (code "64") (name "unconnected-(U2-RI{slash}CLK-Pad2)") (class "Default")
      (node (ref "U2") (pin "2") (pinfunction "RI/CLK_2") (pintype "unspecified+no_connect"))
    )
    (net (code "65") (name "unconnected-(U2-SUSPEND-Pad12)") (class "Default")
      (node (ref "U2") (pin "12") (pinfunction "SUSPEND_12") (pintype "unspecified+no_connect"))
    )
    (net (code "66") (name "unconnected-(U3-NC-Pad17)") (class "Default")
      (node (ref "U3") (pin "17") (pinfunction "NC_17") (pintype "unspecified+no_connect"))
    )
    (net (code "67") (name "unconnected-(U3-NC-Pad18)") (class "Default")
      (node (ref "U3") (pin "18") (pinfunction "NC_18") (pintype "unspecified+no_connect"))
    )
    (net (code "68") (name "unconnected-(U3-NC-Pad19)") (class "Default")
      (node (ref "U3") (pin "19") (pinfunction "NC_19") (pintype "unspecified+no_connect"))
    )
    (net (code "69") (name "unconnected-(U3-NC-Pad20)") (class "Default")
      (node (ref "U3") (pin "20") (pinfunction "NC_20") (pintype "unspecified+no_connect"))
    )
    (net (code "70") (name "unconnected-(U3-NC-Pad21)") (class "Default")
      (node (ref "U3") (pin "21") (pinfunction "NC_21") (pintype "unspecified+no_connect"))
    )
    (net (code "71") (name "unconnected-(U3-NC-Pad22)") (class "Default")
      (node (ref "U3") (pin "22") (pinfunction "NC_22") (pintype "unspecified+no_connect"))
    )
    (net (code "72") (name "unconnected-(U3-NC-Pad32)") (class "Default")
      (node (ref "U3") (pin "32") (pinfunction "NC_32") (pintype "unspecified+no_connect"))
    )
  )
)
